# Beta.net
KiCad netlist of a schematic drawn in EAGLE
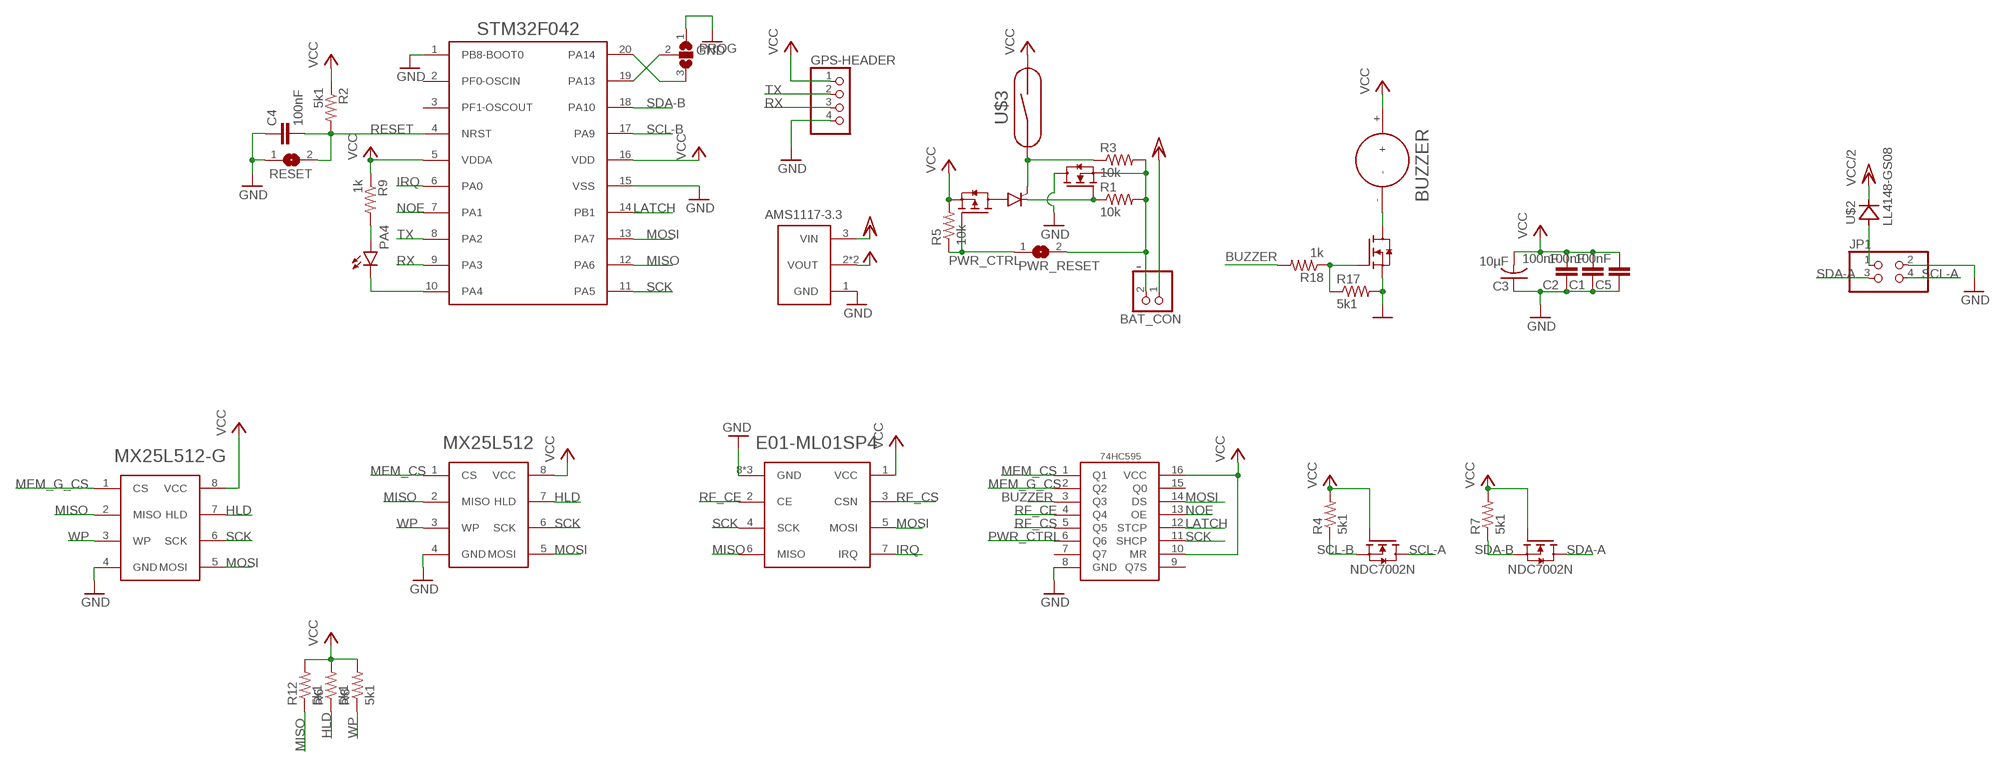
[diagram p0: schematic, sheet 1]

(export (version "E")
  (design (tool "Eeschema 10.0.6"))
  (components
    (comp (ref "74HC595")
      (value "74HC595SOIC16")
      (footprint "eagle-import:SOIC16")
      (libsource (lib "eagle-import") (part "74HC595SOIC16"))
    )
    (comp (ref "AMS1117-3.3")
      (value "AMS1117")
      (footprint "eagle-import:SOT223")
      (libsource (lib "eagle-import") (part "AMS1117"))
    )
    (comp (ref "AO3407")
      (value "AO3407A")
      (footprint "eagle-import:SOT23-3")
      (libsource (lib "eagle-import") (part "AO3407A"))
    )
    (comp (ref "BAT_CON")
      (value "PINHD-1X2")
      (footprint "eagle-import:1X02")
      (libsource (lib "eagle-import") (part "PINHD-1X2"))
    )
    (comp (ref "BUZ")
      (value "SI2302CDS")
      (footprint "eagle-import:SOT23-3")
      (libsource (lib "eagle-import") (part "SI2302CDS"))
    )
    (comp (ref "BUZZER")
      (value "BUZZER-5V")
      (footprint "eagle-import:BUZZER")
      (libsource (lib "eagle-import") (part "BUZZER-5V"))
    )
    (comp (ref "C1")
      (value "100nF")
      (footprint "eagle-import:C0603")
      (libsource (lib "eagle-import") (part "C-EUC0603"))
    )
    (comp (ref "C2")
      (value "100nF")
      (footprint "eagle-import:C0603")
      (libsource (lib "eagle-import") (part "C-EUC0603"))
    )
    (comp (ref "C3")
      (value "10µF")
      (footprint "eagle-import:C1206")
      (libsource (lib "eagle-import") (part "C-USC1206"))
    )
    (comp (ref "C4")
      (value "100nF")
      (footprint "eagle-import:C0603")
      (libsource (lib "eagle-import") (part "C-EUC0603"))
    )
    (comp (ref "C5")
      (value "100nF")
      (footprint "eagle-import:C0603")
      (libsource (lib "eagle-import") (part "C-EUC0603"))
    )
    (comp (ref "E01-ML01SP4")
      (value "E01-ML01SP4")
      (footprint "eagle-import:E01-ML01SP4")
      (libsource (lib "eagle-import") (part "E01-ML01SP4"))
    )
    (comp (ref "GPS-HEADER")
      (value "PINHD-1X4")
      (footprint "eagle-import:1X04")
      (libsource (lib "eagle-import") (part "PINHD-1X4"))
    )
    (comp (ref "JP1")
      (value "PINHD-2X2")
      (footprint "eagle-import:2X02")
      (libsource (lib "eagle-import") (part "PINHD-2X2"))
    )
    (comp (ref "MX25L512")
      (value "MX25L25645")
      (footprint "eagle-import:SOP8")
      (libsource (lib "eagle-import") (part "MX25L25645"))
    )
    (comp (ref "MX25L512-G")
      (value "MX25L25645")
      (footprint "eagle-import:SOP8")
      (libsource (lib "eagle-import") (part "MX25L25645"))
    )
    (comp (ref "NDC7002N")
      (value "NDC7002N")
      (footprint "eagle-import:SOT-23-6")
      (libsource (lib "eagle-import") (part "NDC7002N"))
    )
    (comp (ref "P0102BL")
      (value "P0102BL")
      (footprint "eagle-import:SOT23-3")
      (libsource (lib "eagle-import") (part "P0102BL"))
    )
    (comp (ref "PA4")
      (value "LEDCHIPLED_0603")
      (footprint "eagle-import:CHIPLED_0603")
      (libsource (lib "eagle-import") (part "LEDCHIPLED_0603"))
    )
    (comp (ref "PROG")
      (value "SJ2W")
      (footprint "eagle-import:SJ_2")
      (libsource (lib "eagle-import") (part "SJ2W"))
    )
    (comp (ref "PWR_RESET")
      (value "SJ")
      (footprint "eagle-import:SJ")
      (libsource (lib "eagle-import") (part "SJ"))
    )
    (comp (ref "R1")
      (value "10k")
      (footprint "eagle-import:R0603")
      (libsource (lib "eagle-import") (part "R-US_R0603"))
    )
    (comp (ref "R2")
      (value "5k1")
      (footprint "eagle-import:R0603")
      (libsource (lib "eagle-import") (part "R-US_R0603"))
    )
    (comp (ref "R3")
      (value "10k")
      (footprint "eagle-import:R0603")
      (libsource (lib "eagle-import") (part "R-US_R0603"))
    )
    (comp (ref "R4")
      (value "5k1")
      (footprint "eagle-import:R0603")
      (libsource (lib "eagle-import") (part "R-US_R0603"))
    )
    (comp (ref "R5")
      (value "10k")
      (footprint "eagle-import:R0603")
      (libsource (lib "eagle-import") (part "R-US_R0603"))
    )
    (comp (ref "R6")
      (value "5k1")
      (footprint "eagle-import:R0603")
      (libsource (lib "eagle-import") (part "R-US_R0603"))
    )
    (comp (ref "R7")
      (value "5k1")
      (footprint "eagle-import:R0603")
      (libsource (lib "eagle-import") (part "R-US_R0603"))
    )
    (comp (ref "R8")
      (value "5k1")
      (footprint "eagle-import:R0603")
      (libsource (lib "eagle-import") (part "R-US_R0603"))
    )
    (comp (ref "R9")
      (value "1k")
      (footprint "eagle-import:R0603")
      (libsource (lib "eagle-import") (part "R-US_R0603"))
    )
    (comp (ref "R12")
      (value "5k1")
      (footprint "eagle-import:R0603")
      (libsource (lib "eagle-import") (part "R-US_R0603"))
    )
    (comp (ref "R17")
      (value "5k1")
      (footprint "eagle-import:R0603")
      (libsource (lib "eagle-import") (part "R-US_R0603"))
    )
    (comp (ref "R18")
      (value "1k")
      (footprint "eagle-import:R0603")
      (libsource (lib "eagle-import") (part "R-US_R0603"))
    )
    (comp (ref "RESET")
      (value "SJ")
      (footprint "eagle-import:SJ")
      (libsource (lib "eagle-import") (part "SJ"))
    )
    (comp (ref "SI2302")
      (value "SI2302CDS")
      (footprint "eagle-import:SOT23-3")
      (libsource (lib "eagle-import") (part "SI2302CDS"))
    )
    (comp (ref "STM32F042")
      (value "STM32F042F6P6")
      (footprint "eagle-import:TSSOP-20")
      (libsource (lib "eagle-import") (part "STM32F042F6P6"))
    )
    (comp (ref "U$2")
      (value "LL4148-GS08")
      (footprint "eagle-import:SOD-80")
      (libsource (lib "eagle-import") (part "LL4148-GS08"))
    )
    (comp (ref "U$3")
      (value "МКА-07101")
      (footprint "eagle-import:МКА-07101")
      (libsource (lib "eagle-import") (part "МКА-07101"))
    )
  )
  (nets
    (net (code "1") (name "/BUZZER") (class "Default")
      (node (ref "74HC595") (pin "3") (pinfunction "Q3_3") (pintype "bidirectional"))
      (node (ref "R18") (pin "2") (pinfunction "2_2") (pintype "passive"))
    )
    (net (code "2") (name "/HLD") (class "Default")
      (node (ref "MX25L512") (pin "7") (pinfunction "HLD_7") (pintype "bidirectional"))
      (node (ref "MX25L512-G") (pin "7") (pinfunction "HLD_7") (pintype "bidirectional"))
      (node (ref "R6") (pin "1") (pinfunction "1_1") (pintype "passive"))
    )
    (net (code "3") (name "/IRQ") (class "Default")
      (node (ref "E01-ML01SP4") (pin "7") (pinfunction "IRQ_7") (pintype "bidirectional"))
      (node (ref "STM32F042") (pin "6") (pinfunction "PA0_6") (pintype "bidirectional"))
    )
    (net (code "4") (name "/LATCH") (class "Default")
      (node (ref "74HC595") (pin "12") (pinfunction "STCP_12") (pintype "bidirectional"))
      (node (ref "STM32F042") (pin "14") (pinfunction "PB1_14") (pintype "bidirectional"))
    )
    (net (code "5") (name "/MEM_CS") (class "Default")
      (node (ref "74HC595") (pin "1") (pinfunction "Q1_1") (pintype "bidirectional"))
      (node (ref "MX25L512") (pin "1") (pinfunction "CS_1") (pintype "bidirectional"))
    )
    (net (code "6") (name "/MEM_G_CS") (class "Default")
      (node (ref "74HC595") (pin "2") (pinfunction "Q2_2") (pintype "bidirectional"))
      (node (ref "MX25L512-G") (pin "1") (pinfunction "CS_1") (pintype "bidirectional"))
    )
    (net (code "7") (name "/MISO") (class "Default")
      (node (ref "E01-ML01SP4") (pin "6") (pinfunction "MISO_6") (pintype "bidirectional"))
      (node (ref "MX25L512") (pin "2") (pinfunction "MISO_2") (pintype "bidirectional"))
      (node (ref "MX25L512-G") (pin "2") (pinfunction "MISO_2") (pintype "bidirectional"))
      (node (ref "R12") (pin "1") (pinfunction "1_1") (pintype "passive"))
      (node (ref "STM32F042") (pin "12") (pinfunction "PA6_12") (pintype "bidirectional"))
    )
    (net (code "8") (name "/MOSI") (class "Default")
      (node (ref "74HC595") (pin "14") (pinfunction "DS_14") (pintype "bidirectional"))
      (node (ref "E01-ML01SP4") (pin "5") (pinfunction "MOSI_5") (pintype "bidirectional"))
      (node (ref "MX25L512") (pin "5") (pinfunction "MOSI_5") (pintype "bidirectional"))
      (node (ref "MX25L512-G") (pin "5") (pinfunction "MOSI_5") (pintype "bidirectional"))
      (node (ref "STM32F042") (pin "13") (pinfunction "PA7_13") (pintype "bidirectional"))
    )
    (net (code "9") (name "/NOE") (class "Default")
      (node (ref "74HC595") (pin "13") (pinfunction "OE_13") (pintype "bidirectional"))
      (node (ref "STM32F042") (pin "7") (pinfunction "PA1_7") (pintype "bidirectional"))
    )
    (net (code "10") (name "/PWR_CTRL") (class "Default")
      (node (ref "74HC595") (pin "6") (pinfunction "Q6_6") (pintype "bidirectional"))
      (node (ref "AO3407") (pin "1") (pinfunction "G_1") (pintype "passive"))
      (node (ref "PWR_RESET") (pin "1") (pinfunction "1_1") (pintype "passive"))
      (node (ref "R5") (pin "1") (pinfunction "1_1") (pintype "passive"))
    )
    (net (code "11") (name "/RESET") (class "Default")
      (node (ref "C4") (pin "2") (pinfunction "2_2") (pintype "passive"))
      (node (ref "R2") (pin "2") (pinfunction "2_2") (pintype "passive"))
      (node (ref "RESET") (pin "2") (pinfunction "2_2") (pintype "passive"))
      (node (ref "STM32F042") (pin "4") (pinfunction "NRST_4") (pintype "bidirectional"))
    )
    (net (code "12") (name "/RF_CE") (class "Default")
      (node (ref "74HC595") (pin "4") (pinfunction "Q4_4") (pintype "bidirectional"))
      (node (ref "E01-ML01SP4") (pin "2") (pinfunction "CE_2") (pintype "bidirectional"))
    )
    (net (code "13") (name "/RF_CS") (class "Default")
      (node (ref "74HC595") (pin "5") (pinfunction "Q5_5") (pintype "bidirectional"))
      (node (ref "E01-ML01SP4") (pin "3") (pinfunction "CSN_3") (pintype "bidirectional"))
    )
    (net (code "14") (name "/RX") (class "Default")
      (node (ref "GPS-HEADER") (pin "3") (pinfunction "3_3") (pintype "passive"))
      (node (ref "STM32F042") (pin "9") (pinfunction "PA3_9") (pintype "bidirectional"))
    )
    (net (code "15") (name "/SCK") (class "Default")
      (node (ref "74HC595") (pin "11") (pinfunction "SHCP_11") (pintype "bidirectional"))
      (node (ref "E01-ML01SP4") (pin "4") (pinfunction "SCK_4") (pintype "bidirectional"))
      (node (ref "MX25L512") (pin "6") (pinfunction "SCK_6") (pintype "bidirectional"))
      (node (ref "MX25L512-G") (pin "6") (pinfunction "SCK_6") (pintype "bidirectional"))
      (node (ref "STM32F042") (pin "11") (pinfunction "PA5_11") (pintype "bidirectional"))
    )
    (net (code "16") (name "/SCL-A") (class "Default")
      (node (ref "JP1") (pin "4") (pinfunction "4_4") (pintype "passive"))
      (node (ref "NDC7002N") (pin "6") (pinfunction "D1_6") (pintype "passive"))
    )
    (net (code "17") (name "/SCL-B") (class "Default")
      (node (ref "NDC7002N") (pin "5") (pinfunction "S1_5") (pintype "passive"))
      (node (ref "R4") (pin "1") (pinfunction "1_1") (pintype "passive"))
      (node (ref "STM32F042") (pin "17") (pinfunction "PA9_17") (pintype "bidirectional"))
    )
    (net (code "18") (name "/SDA-A") (class "Default")
      (node (ref "JP1") (pin "3") (pinfunction "3_3") (pintype "passive"))
      (node (ref "NDC7002N") (pin "4") (pinfunction "D2_4") (pintype "passive"))
    )
    (net (code "19") (name "/SDA-B") (class "Default")
      (node (ref "NDC7002N") (pin "2") (pinfunction "S2_2") (pintype "passive"))
      (node (ref "R7") (pin "1") (pinfunction "1_1") (pintype "passive"))
      (node (ref "STM32F042") (pin "18") (pinfunction "PA10_18") (pintype "bidirectional"))
    )
    (net (code "20") (name "/TX") (class "Default")
      (node (ref "GPS-HEADER") (pin "2") (pinfunction "2_2") (pintype "passive"))
      (node (ref "STM32F042") (pin "8") (pinfunction "PA2_8") (pintype "bidirectional"))
    )
    (net (code "21") (name "/WP") (class "Default")
      (node (ref "MX25L512") (pin "3") (pinfunction "WP_3") (pintype "bidirectional"))
      (node (ref "MX25L512-G") (pin "3") (pinfunction "WP_3") (pintype "bidirectional"))
      (node (ref "R8") (pin "1") (pinfunction "1_1") (pintype "passive"))
    )
    (net (code "22") (name "GND") (class "Default")
      (node (ref "74HC595") (pin "8") (pinfunction "GND_8") (pintype "bidirectional"))
      (node (ref "AMS1117-3.3") (pin "1") (pinfunction "GND_1") (pintype "bidirectional"))
      (node (ref "BUZ") (pin "2") (pinfunction "S_2") (pintype "passive"))
      (node (ref "C1") (pin "1") (pinfunction "1_1") (pintype "passive"))
      (node (ref "C2") (pin "1") (pinfunction "1_1") (pintype "passive"))
      (node (ref "C3") (pin "1") (pinfunction "1_1") (pintype "passive"))
      (node (ref "C4") (pin "1") (pinfunction "1_1") (pintype "passive"))
      (node (ref "C5") (pin "1") (pinfunction "1_1") (pintype "passive"))
      (node (ref "E01-ML01SP4") (pin "10") (pinfunction "GND_10") (pintype "bidirectional"))
      (node (ref "E01-ML01SP4") (pin "8") (pinfunction "GND_8") (pintype "bidirectional"))
      (node (ref "E01-ML01SP4") (pin "9") (pinfunction "GND_9") (pintype "bidirectional"))
      (node (ref "GPS-HEADER") (pin "4") (pinfunction "4_4") (pintype "passive"))
      (node (ref "JP1") (pin "2") (pinfunction "2_2") (pintype "passive"))
      (node (ref "MX25L512") (pin "4") (pinfunction "GND_4") (pintype "bidirectional"))
      (node (ref "MX25L512-G") (pin "4") (pinfunction "GND_4") (pintype "bidirectional"))
      (node (ref "PROG") (pin "1") (pinfunction "1_1") (pintype "passive"))
      (node (ref "R17") (pin "2") (pinfunction "2_2") (pintype "passive"))
      (node (ref "RESET") (pin "1") (pinfunction "1_1") (pintype "passive"))
      (node (ref "SI2302") (pin "3") (pinfunction "D_3") (pintype "passive"))
      (node (ref "STM32F042") (pin "1") (pinfunction "PB8-BOOT0_1") (pintype "bidirectional"))
      (node (ref "STM32F042") (pin "15") (pinfunction "VSS_15") (pintype "bidirectional"))
    )
    (net (code "23") (name "Net-(AO3407-D)") (class "Default")
      (node (ref "AO3407") (pin "3") (pinfunction "D_3") (pintype "passive"))
      (node (ref "P0102BL") (pin "3") (pinfunction "A_3") (pintype "passive"))
    )
    (net (code "24") (name "Net-(BUZ-D)") (class "Default")
      (node (ref "BUZ") (pin "3") (pinfunction "D_3") (pintype "passive"))
      (node (ref "BUZZER") (pin "-") (pinfunction "-_-") (pintype "bidirectional"))
    )
    (net (code "25") (name "Net-(BUZ-G)") (class "Default")
      (node (ref "BUZ") (pin "1") (pinfunction "G_1") (pintype "passive"))
      (node (ref "R17") (pin "1") (pinfunction "1_1") (pintype "passive"))
      (node (ref "R18") (pin "1") (pinfunction "1_1") (pintype "passive"))
    )
    (net (code "26") (name "Net-(P0102BL-C)") (class "Default")
      (node (ref "P0102BL") (pin "1") (pinfunction "C_1") (pintype "passive"))
      (node (ref "R1") (pin "1") (pinfunction "1_1") (pintype "passive"))
      (node (ref "SI2302") (pin "1") (pinfunction "G_1") (pintype "passive"))
    )
    (net (code "27") (name "Net-(P0102BL-G)") (class "Default")
      (node (ref "P0102BL") (pin "2") (pinfunction "G_2") (pintype "passive"))
      (node (ref "R3") (pin "1") (pinfunction "1_1") (pintype "passive"))
      (node (ref "U$3") (pin "1") (pinfunction "1_1") (pintype "bidirectional"))
    )
    (net (code "28") (name "Net-(PA4-PadA)") (class "Default")
      (node (ref "PA4") (pin "A") (pinfunction "A_A") (pintype "passive"))
      (node (ref "R9") (pin "2") (pinfunction "2_2") (pintype "passive"))
    )
    (net (code "29") (name "Net-(SI2302-S)") (class "Default")
      (node (ref "BAT_CON") (pin "2") (pinfunction "2_2") (pintype "passive"))
      (node (ref "PWR_RESET") (pin "2") (pinfunction "2_2") (pintype "passive"))
      (node (ref "R1") (pin "2") (pinfunction "2_2") (pintype "passive"))
      (node (ref "R3") (pin "2") (pinfunction "2_2") (pintype "passive"))
      (node (ref "SI2302") (pin "2") (pinfunction "S_2") (pintype "passive"))
    )
    (net (code "30") (name "Net-(STM32F042-PA4)") (class "Default")
      (node (ref "PA4") (pin "C") (pinfunction "C_C") (pintype "passive"))
      (node (ref "STM32F042") (pin "10") (pinfunction "PA4_10") (pintype "bidirectional"))
    )
    (net (code "31") (name "Net-(STM32F042-PA13)") (class "Default")
      (node (ref "PROG") (pin "2") (pinfunction "2_2") (pintype "passive"))
      (node (ref "STM32F042") (pin "19") (pinfunction "PA13_19") (pintype "bidirectional"))
    )
    (net (code "32") (name "Net-(STM32F042-PA14)") (class "Default")
      (node (ref "PROG") (pin "3") (pinfunction "3_3") (pintype "passive"))
      (node (ref "STM32F042") (pin "20") (pinfunction "PA14_20") (pintype "bidirectional"))
    )
    (net (code "33") (name "Net-(U$2-A)") (class "Default")
      (node (ref "JP1") (pin "1") (pinfunction "1_1") (pintype "passive"))
      (node (ref "U$2") (pin "1") (pinfunction "A_1") (pintype "passive"))
    )
    (net (code "34") (name "VCC") (class "Default")
      (node (ref "74HC595") (pin "10") (pinfunction "MR_10") (pintype "bidirectional"))
      (node (ref "74HC595") (pin "16") (pinfunction "VCC_16") (pintype "bidirectional"))
      (node (ref "AMS1117-3.3") (pin "2") (pinfunction "VOUT_2") (pintype "bidirectional"))
      (node (ref "AMS1117-3.3") (pin "4") (pinfunction "VOUT_4") (pintype "bidirectional"))
      (node (ref "AO3407") (pin "2") (pinfunction "S_2") (pintype "passive"))
      (node (ref "BUZZER") (pin "+") (pinfunction "+_+") (pintype "bidirectional"))
      (node (ref "C1") (pin "2") (pinfunction "2_2") (pintype "passive"))
      (node (ref "C2") (pin "2") (pinfunction "2_2") (pintype "passive"))
      (node (ref "C3") (pin "2") (pinfunction "2_2") (pintype "passive"))
      (node (ref "C5") (pin "2") (pinfunction "2_2") (pintype "passive"))
      (node (ref "E01-ML01SP4") (pin "1") (pinfunction "VCC_1") (pintype "bidirectional"))
      (node (ref "GPS-HEADER") (pin "1") (pinfunction "1_1") (pintype "passive"))
      (node (ref "MX25L512") (pin "8") (pinfunction "VCC_8") (pintype "bidirectional"))
      (node (ref "MX25L512-G") (pin "8") (pinfunction "VCC_8") (pintype "bidirectional"))
      (node (ref "NDC7002N") (pin "1") (pinfunction "G1_1") (pintype "passive"))
      (node (ref "NDC7002N") (pin "3") (pinfunction "G2_3") (pintype "passive"))
      (node (ref "R12") (pin "2") (pinfunction "2_2") (pintype "passive"))
      (node (ref "R2") (pin "1") (pinfunction "1_1") (pintype "passive"))
      (node (ref "R4") (pin "2") (pinfunction "2_2") (pintype "passive"))
      (node (ref "R5") (pin "2") (pinfunction "2_2") (pintype "passive"))
      (node (ref "R6") (pin "2") (pinfunction "2_2") (pintype "passive"))
      (node (ref "R7") (pin "2") (pinfunction "2_2") (pintype "passive"))
      (node (ref "R8") (pin "2") (pinfunction "2_2") (pintype "passive"))
      (node (ref "R9") (pin "1") (pinfunction "1_1") (pintype "passive"))
      (node (ref "STM32F042") (pin "16") (pinfunction "VDD_16") (pintype "bidirectional"))
      (node (ref "STM32F042") (pin "5") (pinfunction "VDDA_5") (pintype "bidirectional"))
      (node (ref "U$3") (pin "2") (pinfunction "2_2") (pintype "bidirectional"))
    )
    (net (code "35") (name "VCC{slash}2") (class "Default")
      (node (ref "AMS1117-3.3") (pin "3") (pinfunction "VIN_3") (pintype "bidirectional"))
      (node (ref "BAT_CON") (pin "1") (pinfunction "1_1") (pintype "passive"))
      (node (ref "U$2") (pin "2") (pinfunction "C_2") (pintype "passive"))
    )
    (net (code "36") (name "unconnected-(74HC595-Q0-Pad15)") (class "Default")
      (node (ref "74HC595") (pin "15") (pinfunction "Q0_15") (pintype "bidirectional"))
    )
    (net (code "37") (name "unconnected-(74HC595-Q7-Pad7)") (class "Default")
      (node (ref "74HC595") (pin "7") (pinfunction "Q7_7") (pintype "bidirectional"))
    )
    (net (code "38") (name "unconnected-(74HC595-Q7S-Pad9)") (class "Default")
      (node (ref "74HC595") (pin "9") (pinfunction "Q7S_9") (pintype "bidirectional"))
    )
    (net (code "39") (name "unconnected-(STM32F042-PF0-OSCIN-Pad2)") (class "Default")
      (node (ref "STM32F042") (pin "2") (pinfunction "PF0-OSCIN_2") (pintype "bidirectional"))
    )
    (net (code "40") (name "unconnected-(STM32F042-PF1-OSCOUT-Pad3)") (class "Default")
      (node (ref "STM32F042") (pin "3") (pinfunction "PF1-OSCOUT_3") (pintype "bidirectional"))
    )
  )
)
